# ExternalRam.net
KiCad netlist of a schematic drawn in Altium Designer
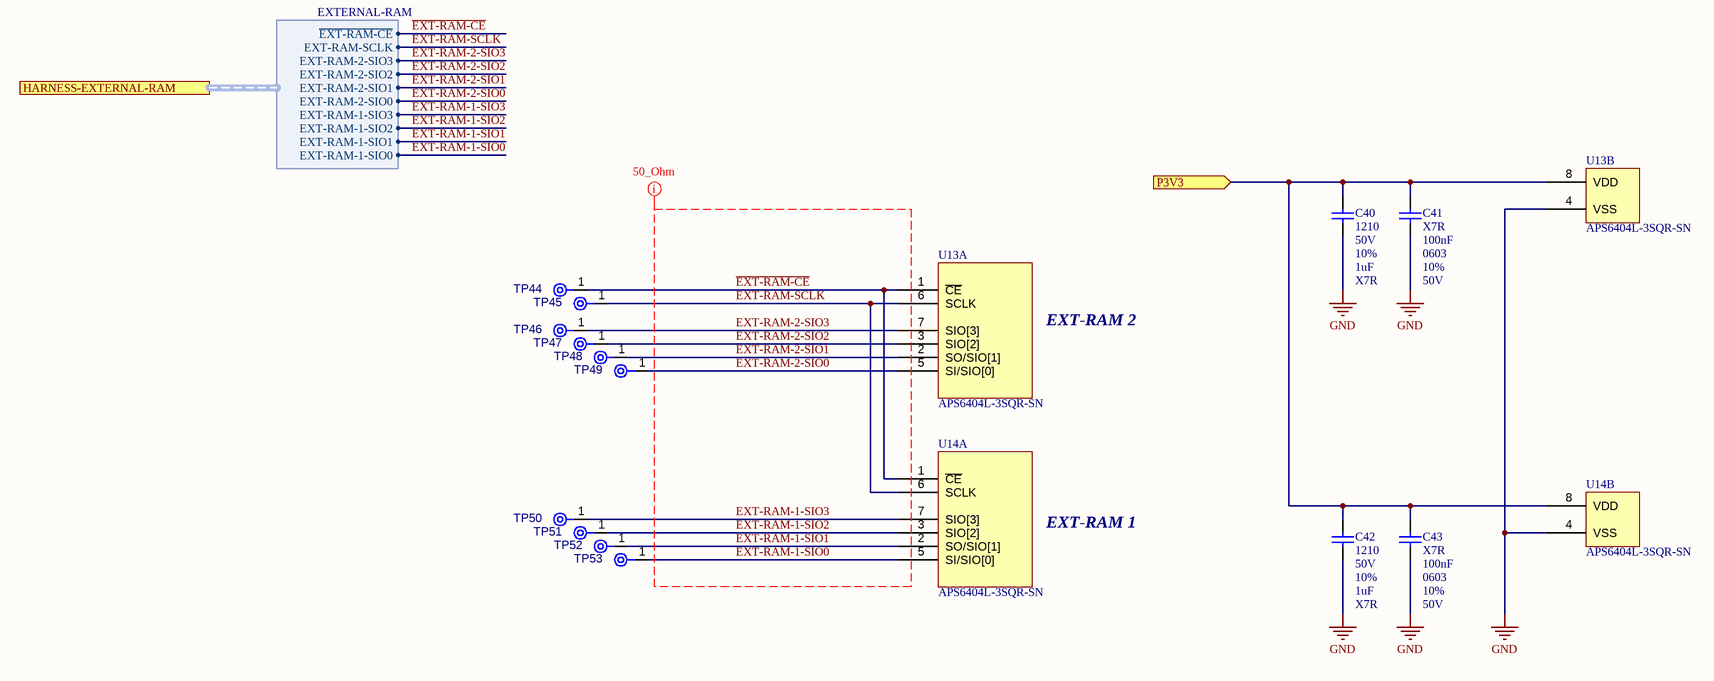
[diagram p0: ExternalRam.SchDoc]

(export (version "E")
  (design (tool "Eeschema 10.0.6"))
  (components
    (comp (ref "C40")
      (value "1uF")
      (footprint "CAPC3225X270X30ML30")
      (description "Chip Capacitor, 1uF, 10%, 50 V, X7R 1210 (3225 Metric)")
      (fields
        (field (name "CASE/PACKAGE") "1210")
        (field (name "VOLTAGE RATING") "50V")
        (field (name "TOLERANCE") "10%")
        (field (name "DIELECTRIC") "X7R")
        (field (name "Comment") "Capacitor 1uF 10%, 50V, X7R, 1210")
      )
      (libsource (lib "Applied Physics Lab") (part "CAP-NP-2"))
    )
    (comp (ref "C41")
      (value "100nF")
      (footprint "CAPC1608X90X40ML10T20")
      (description "Chip Capacitor, 100nF, +/- 10%, 50 V, X7R 0603 (1608 Metric)")
      (fields
        (field (name "DIELECTRIC") "X7R")
        (field (name "CASE/PACKAGE") "0603")
        (field (name "TOLERANCE") "10%")
        (field (name "VOLTAGE RATING") "50V")
        (field (name "Comment") "Capacitor 100nF +/- 10%, 50V, X7R, 0603")
      )
      (libsource (lib "Applied Physics Lab") (part "CAP-NP-2"))
    )
    (comp (ref "C42")
      (value "1uF")
      (footprint "CAPC3225X270X30ML30")
      (description "Chip Capacitor, 1uF, 10%, 50 V, X7R 1210 (3225 Metric)")
      (fields
        (field (name "CASE/PACKAGE") "1210")
        (field (name "VOLTAGE RATING") "50V")
        (field (name "TOLERANCE") "10%")
        (field (name "DIELECTRIC") "X7R")
        (field (name "Comment") "Capacitor 1uF 10%, 50V, X7R, 1210")
      )
      (libsource (lib "Applied Physics Lab") (part "CAP-NP-2"))
    )
    (comp (ref "C43")
      (value "100nF")
      (footprint "CAPC1608X90X40ML10T20")
      (description "Chip Capacitor, 100nF, +/- 10%, 50 V, X7R 0603 (1608 Metric)")
      (fields
        (field (name "DIELECTRIC") "X7R")
        (field (name "CASE/PACKAGE") "0603")
        (field (name "TOLERANCE") "10%")
        (field (name "VOLTAGE RATING") "50V")
        (field (name "Comment") "Capacitor 100nF +/- 10%, 50V, X7R, 0603")
      )
      (libsource (lib "Applied Physics Lab") (part "CAP-NP-2"))
    )
    (comp (ref "TP44")
      (value "TPAD6R-CIRCLED")
      (footprint "TP06R - Circled")
      (description "0.6mm round with a silkscreen circle.")
      (libsource (lib "Applied Physics Lab") (part "CMP-001-0001-4"))
    )
    (comp (ref "TP45")
      (value "TPAD6R-CIRCLED")
      (footprint "TP06R - Circled")
      (description "0.6mm round with a silkscreen circle.")
      (libsource (lib "Applied Physics Lab") (part "CMP-001-0001-4"))
    )
    (comp (ref "TP46")
      (value "TPAD6R-CIRCLED")
      (footprint "TP06R - Circled")
      (description "0.6mm round with a silkscreen circle.")
      (libsource (lib "Applied Physics Lab") (part "CMP-001-0001-4"))
    )
    (comp (ref "TP47")
      (value "TPAD6R-CIRCLED")
      (footprint "TP06R - Circled")
      (description "0.6mm round with a silkscreen circle.")
      (libsource (lib "Applied Physics Lab") (part "CMP-001-0001-4"))
    )
    (comp (ref "TP48")
      (value "TPAD6R-CIRCLED")
      (footprint "TP06R - Circled")
      (description "0.6mm round with a silkscreen circle.")
      (libsource (lib "Applied Physics Lab") (part "CMP-001-0001-4"))
    )
    (comp (ref "TP49")
      (value "TPAD6R-CIRCLED")
      (footprint "TP06R - Circled")
      (description "0.6mm round with a silkscreen circle.")
      (libsource (lib "Applied Physics Lab") (part "CMP-001-0001-4"))
    )
    (comp (ref "TP50")
      (value "TPAD6R-CIRCLED")
      (footprint "TP06R - Circled")
      (description "0.6mm round with a silkscreen circle.")
      (libsource (lib "Applied Physics Lab") (part "CMP-001-0001-4"))
    )
    (comp (ref "TP51")
      (value "TPAD6R-CIRCLED")
      (footprint "TP06R - Circled")
      (description "0.6mm round with a silkscreen circle.")
      (libsource (lib "Applied Physics Lab") (part "CMP-001-0001-4"))
    )
    (comp (ref "TP52")
      (value "TPAD6R-CIRCLED")
      (footprint "TP06R - Circled")
      (description "0.6mm round with a silkscreen circle.")
      (libsource (lib "Applied Physics Lab") (part "CMP-001-0001-4"))
    )
    (comp (ref "TP53")
      (value "TPAD6R-CIRCLED")
      (footprint "TP06R - Circled")
      (description "0.6mm round with a silkscreen circle.")
      (libsource (lib "Applied Physics Lab") (part "CMP-001-0001-4"))
    )
    (comp (ref "U13")
      (value "APS6404L-3SQR-SN")
      (footprint "SOP127P600X175-8M")
      (description "8MX8, Cmos, PDSO8")
      (fields (field (name "MANUFACTURER") "AP Memory"))
      (libsource (lib "Applied Physics Lab") (part "APS6404L-3SQR-SN-Symbol-1"))
    )
    (comp (ref "U14")
      (value "APS6404L-3SQR-SN")
      (footprint "SOP127P600X175-8M")
      (description "8MX8, Cmos, PDSO8")
      (fields (field (name "MANUFACTURER") "AP Memory"))
      (libsource (lib "Applied Physics Lab") (part "APS6404L-3SQR-SN-Symbol-1"))
    )
  )
  (nets
    (net (code "2") (name "/EXT-RAM-1-SIO0") (class "Default")
      (node (ref "TP53") (pin "1") (pinfunction "TP_1") (pintype "passive"))
      (node (ref "U14") (pin "5") (pinfunction "SI/SIO[0]_5") (pintype "passive"))
    )
    (net (code "3") (name "/EXT-RAM-1-SIO1") (class "Default")
      (node (ref "TP52") (pin "1") (pinfunction "TP_1") (pintype "passive"))
      (node (ref "U14") (pin "2") (pinfunction "SO/SIO[1]_2") (pintype "passive"))
    )
    (net (code "4") (name "/EXT-RAM-1-SIO2") (class "Default")
      (node (ref "TP51") (pin "1") (pinfunction "TP_1") (pintype "passive"))
      (node (ref "U14") (pin "3") (pinfunction "SIO[2]_3") (pintype "passive"))
    )
    (net (code "5") (name "/EXT-RAM-1-SIO3") (class "Default")
      (node (ref "TP50") (pin "1") (pinfunction "TP_1") (pintype "passive"))
      (node (ref "U14") (pin "7") (pinfunction "SIO[3]_7") (pintype "passive"))
    )
    (net (code "6") (name "/EXT-RAM-2-SIO0") (class "Default")
      (node (ref "TP49") (pin "1") (pinfunction "TP_1") (pintype "passive"))
      (node (ref "U13") (pin "5") (pinfunction "SI/SIO[0]_5") (pintype "passive"))
    )
    (net (code "7") (name "/EXT-RAM-2-SIO1") (class "Default")
      (node (ref "TP48") (pin "1") (pinfunction "TP_1") (pintype "passive"))
      (node (ref "U13") (pin "2") (pinfunction "SO/SIO[1]_2") (pintype "passive"))
    )
    (net (code "8") (name "/EXT-RAM-2-SIO2") (class "Default")
      (node (ref "TP47") (pin "1") (pinfunction "TP_1") (pintype "passive"))
      (node (ref "U13") (pin "3") (pinfunction "SIO[2]_3") (pintype "passive"))
    )
    (net (code "9") (name "/EXT-RAM-2-SIO3") (class "Default")
      (node (ref "TP46") (pin "1") (pinfunction "TP_1") (pintype "passive"))
      (node (ref "U13") (pin "7") (pinfunction "SIO[3]_7") (pintype "passive"))
    )
    (net (code "10") (name "/EXT-RAM-SCLK") (class "Default")
      (node (ref "TP45") (pin "1") (pinfunction "TP_1") (pintype "passive"))
      (node (ref "U13") (pin "6") (pinfunction "SCLK_6") (pintype "passive"))
      (node (ref "U14") (pin "6") (pinfunction "SCLK_6") (pintype "passive"))
    )
    (net (code "11") (name "/P3V3") (class "Default")
      (node (ref "C40") (pin "2") (pinfunction "2_2") (pintype "passive"))
      (node (ref "C41") (pin "2") (pinfunction "2_2") (pintype "passive"))
      (node (ref "C42") (pin "2") (pinfunction "2_2") (pintype "passive"))
      (node (ref "C43") (pin "2") (pinfunction "2_2") (pintype "passive"))
      (node (ref "U13") (pin "8") (pinfunction "VDD_8") (pintype "passive"))
      (node (ref "U14") (pin "8") (pinfunction "VDD_8") (pintype "passive"))
    )
    (net (code "13") (name "/~{EXT-RAM-CE}") (class "Default")
      (node (ref "TP44") (pin "1") (pinfunction "TP_1") (pintype "passive"))
      (node (ref "U13") (pin "1") (pinfunction "~{CE}_1") (pintype "passive"))
      (node (ref "U14") (pin "1") (pinfunction "~{CE}_1") (pintype "passive"))
    )
    (net (code "14") (name "GND") (class "Default")
      (node (ref "C40") (pin "1") (pinfunction "1_1") (pintype "passive"))
      (node (ref "C41") (pin "1") (pinfunction "1_1") (pintype "passive"))
      (node (ref "C42") (pin "1") (pinfunction "1_1") (pintype "passive"))
      (node (ref "C43") (pin "1") (pinfunction "1_1") (pintype "passive"))
      (node (ref "U13") (pin "4") (pinfunction "VSS_4") (pintype "passive"))
      (node (ref "U14") (pin "4") (pinfunction "VSS_4") (pintype "passive"))
    )
  )
)
